# ProPrj_JLINK-OB__2025-09-20.net
KiCad netlist of a schematic drawn in EasyEDA Pro
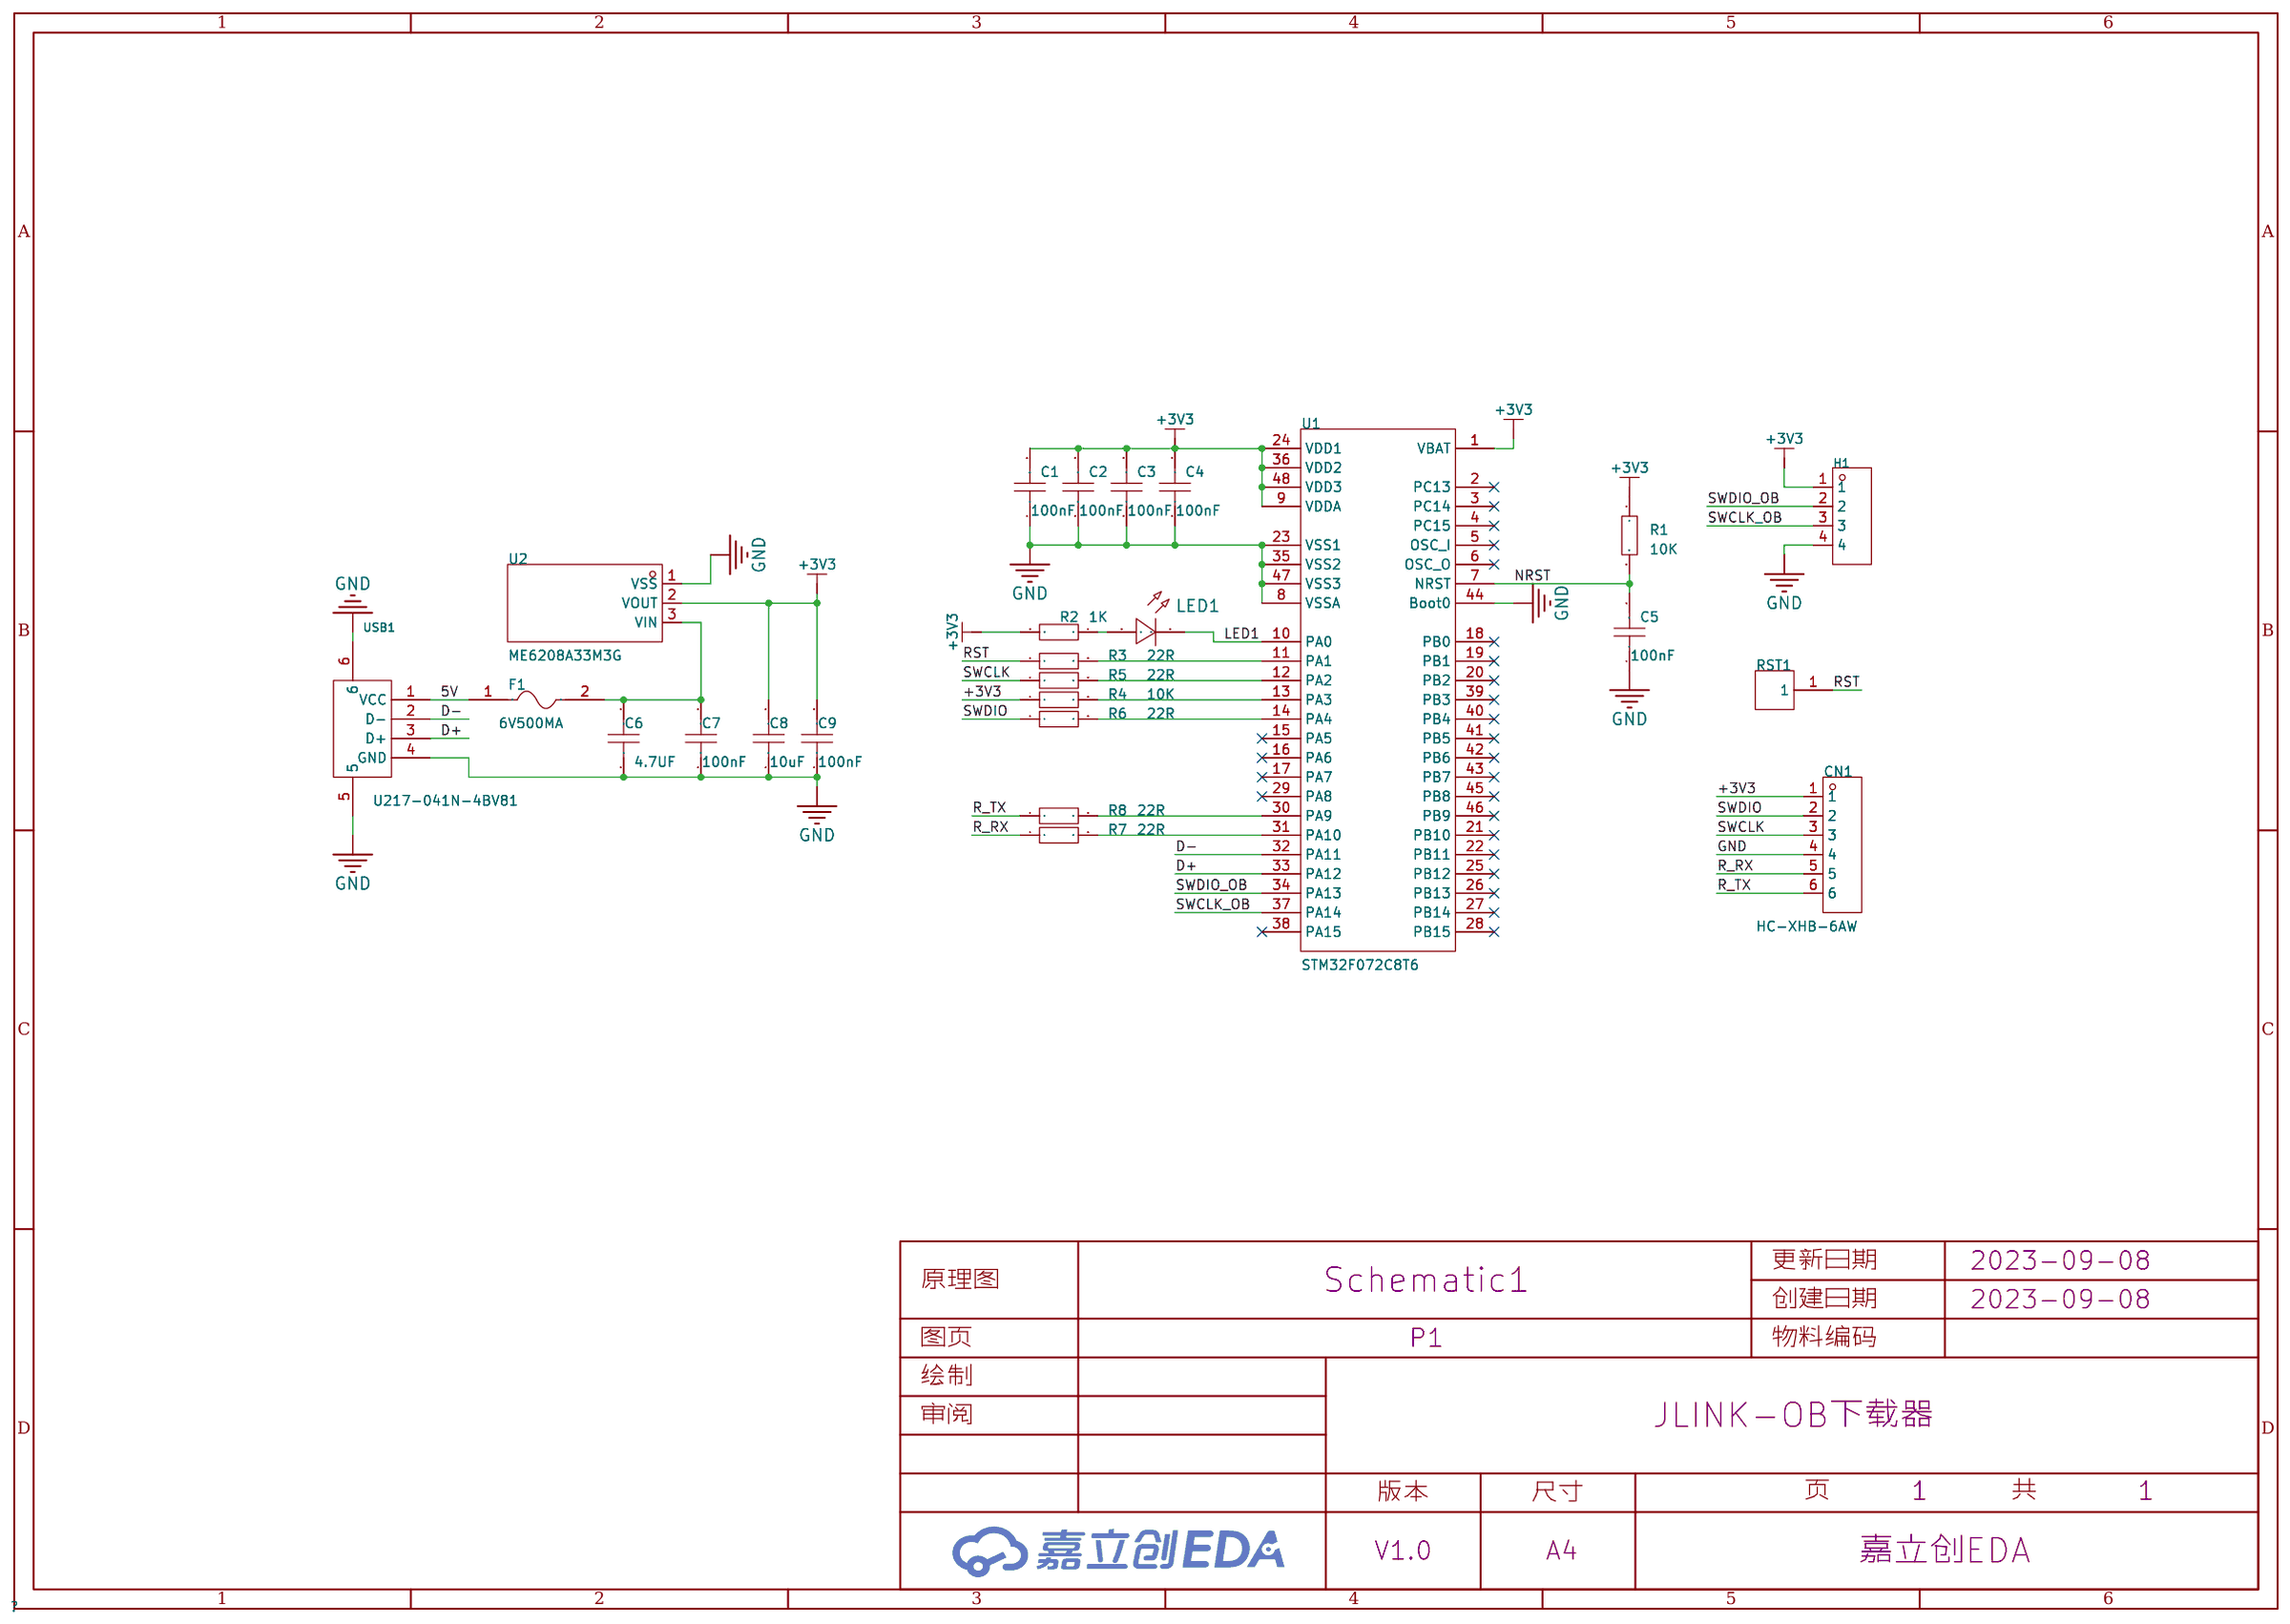
[diagram p0: schematic sheet]

(export (version "E")
  (design (tool "Eeschema 10.0.6"))
  (components
    (comp (ref "C1")
      (value "100nF")
      (footprint "easyedapro:C0603")
      (libsource (lib "easyedapro") (part "CapAcitance"))
    )
    (comp (ref "C2")
      (value "100nF")
      (footprint "easyedapro:C0603")
      (libsource (lib "easyedapro") (part "CapAcitance"))
    )
    (comp (ref "C3")
      (value "100nF")
      (footprint "easyedapro:C0603")
      (libsource (lib "easyedapro") (part "CapAcitance"))
    )
    (comp (ref "C4")
      (value "100nF")
      (footprint "easyedapro:C0603")
      (libsource (lib "easyedapro") (part "CapAcitance"))
    )
    (comp (ref "C5")
      (value "100nF")
      (footprint "easyedapro:C0603")
      (libsource (lib "easyedapro") (part "CapAcitance"))
    )
    (comp (ref "C6")
      (value "4.7UF")
      (footprint "easyedapro:C0603")
      (libsource (lib "easyedapro") (part "CapAcitance"))
    )
    (comp (ref "C7")
      (value "100nF")
      (footprint "easyedapro:C0603")
      (libsource (lib "easyedapro") (part "CapAcitance"))
    )
    (comp (ref "C8")
      (value "10uF")
      (footprint "easyedapro:C0603")
      (libsource (lib "easyedapro") (part "CapAcitance"))
    )
    (comp (ref "C9")
      (value "100nF")
      (footprint "easyedapro:C0603")
      (libsource (lib "easyedapro") (part "CapAcitance"))
    )
    (comp (ref "CN1")
      (value "HC-XHB-6AW")
      (footprint "easyedapro:CONN-TH_6P-P2.50_HCTL_HC-XHB-6AW")
      (description "参考系列:-;间距:2.5mm;插针结构:1x6P;排数:1;每排PIN数:6;行距:-;公母:公型插针;安装方式:弯插;额定电流:3A;工作温度范围:-25°C~+85°C;")
      (fields (field (name "Manufacturer") "HCTL(华灿天禄)"))
      (libsource (lib "easyedapro") (part "HC-XHB-6AW"))
    )
    (comp (ref "F1")
      (value "6V500MA")
      (footprint "easyedapro:F0805")
      (description "最大电压:24V;最大电流:100A;保持电流:100mA;跳闸电流:300mA;")
      (fields (field (name "Manufacturer") "台湾陆海"))
      (libsource (lib "easyedapro") (part "SMD0805-010-24V"))
    )
    (comp (ref "H1")
      (value "~")
      (footprint "easyedapro:HDR-TH_4P-P2.54-V-F")
      (libsource (lib "easyedapro") (part "2.54-1*4P母"))
    )
    (comp (ref "LED1")
      (value "~")
      (footprint "easyedapro:LED_0603")
      (libsource (lib "easyedapro") (part "LED_R"))
    )
    (comp (ref "R1") (value "10K") (footprint "easyedapro:R0603") (libsource (lib "easyedapro") (part "电阻")))
    (comp (ref "R2") (value "1K") (footprint "easyedapro:R0603") (libsource (lib "easyedapro") (part "电阻")))
    (comp (ref "R3") (value "22R") (footprint "easyedapro:R0603") (libsource (lib "easyedapro") (part "电阻")))
    (comp (ref "R4") (value "10K") (footprint "easyedapro:R0603") (libsource (lib "easyedapro") (part "电阻")))
    (comp (ref "R5") (value "22R") (footprint "easyedapro:R0603") (libsource (lib "easyedapro") (part "电阻")))
    (comp (ref "R6") (value "22R") (footprint "easyedapro:R0603") (libsource (lib "easyedapro") (part "电阻")))
    (comp (ref "R7") (value "22R") (footprint "easyedapro:R0603") (libsource (lib "easyedapro") (part "电阻")))
    (comp (ref "R8") (value "22R") (footprint "easyedapro:R0603") (libsource (lib "easyedapro") (part "电阻")))
    (comp (ref "RST1")
      (value "~")
      (footprint "easyedapro:PAD_1.5*1.5MM")
      (libsource (lib "easyedapro") (part "测试点1.5x1.5mm"))
    )
    (comp (ref "U1")
      (value "STM32F072C8T6")
      (footprint "easyedapro:LQFP-48_L7.0-W7.0-P0.50-LS9.0-BL")
      (fields (field (name "Manufacturer") "ST(意法半导体)"))
      (libsource (lib "easyedapro") (part "STM32F072C8T6"))
    )
    (comp (ref "U2")
      (value "ME6208A33M3G")
      (footprint "easyedapro:SOT-23-3_L2.9-W1.3-P1.90-LS2.4-BR")
      (description "输出类型:固定;输出极性:正;最大输入电压:18V;输出电压:3.3V;输出电流:200mA;电源纹波抑制比(PSRR):-;")
      (fields (field (name "Manufacturer") "MICRONE(南京微盟)"))
      (libsource (lib "easyedapro") (part "ME6208A33M3G"))
    )
    (comp (ref "USB1")
      (value "U217-041N-4BV81")
      (footprint "easyedapro:USB-A-SMD_U217-041N-4BV81")
      (fields (field (name "Manufacturer") "XKB Connectivity(中国星坤)"))
      (libsource (lib "easyedapro") (part "U217-04XN-XXR84"))
    )
  )
  (nets
    (net (code "1") (name "+3V3") (class "Default")
      (node (ref "C1") (pin "2") (pinfunction "2_2") (pintype "input"))
      (node (ref "C2") (pin "2") (pinfunction "2_2") (pintype "input"))
      (node (ref "C3") (pin "2") (pinfunction "2_2") (pintype "input"))
      (node (ref "C4") (pin "2") (pinfunction "2_2") (pintype "input"))
      (node (ref "C8") (pin "2") (pinfunction "2_2") (pintype "input"))
      (node (ref "C9") (pin "2") (pinfunction "2_2") (pintype "input"))
      (node (ref "CN1") (pin "1") (pinfunction "1_1") (pintype "input"))
      (node (ref "H1") (pin "1") (pinfunction "1_1") (pintype "input"))
      (node (ref "R1") (pin "1") (pinfunction "1_1") (pintype "input"))
      (node (ref "R2") (pin "2") (pinfunction "2_2") (pintype "input"))
      (node (ref "R4") (pin "1") (pinfunction "1_1") (pintype "input"))
      (node (ref "U1") (pin "1") (pinfunction "VBAT_1") (pintype "input"))
      (node (ref "U1") (pin "24") (pinfunction "VDD1_24") (pintype "input"))
      (node (ref "U1") (pin "36") (pinfunction "VDD2_36") (pintype "input"))
      (node (ref "U1") (pin "48") (pinfunction "VDD3_48") (pintype "input"))
      (node (ref "U1") (pin "9") (pinfunction "VDDA_9") (pintype "input"))
      (node (ref "U2") (pin "2") (pinfunction "VOUT_2") (pintype "input"))
    )
    (net (code "2") (name "/5V") (class "Default")
      (node (ref "F1") (pin "1") (pinfunction "1_1") (pintype "input"))
      (node (ref "USB1") (pin "1") (pinfunction "VCC_1") (pintype "input"))
    )
    (net (code "3") (name "/D+") (class "Default")
      (node (ref "U1") (pin "33") (pinfunction "PA12_33") (pintype "input"))
      (node (ref "USB1") (pin "3") (pinfunction "D+_3") (pintype "input"))
    )
    (net (code "4") (name "/D-") (class "Default")
      (node (ref "U1") (pin "32") (pinfunction "PA11_32") (pintype "input"))
      (node (ref "USB1") (pin "2") (pinfunction "D-_2") (pintype "input"))
    )
    (net (code "5") (name "/LED1") (class "Default")
      (node (ref "LED1") (pin "1") (pinfunction "C_1") (pintype "input"))
      (node (ref "U1") (pin "10") (pinfunction "PA0_10") (pintype "input"))
    )
    (net (code "6") (name "/NRST") (class "Default")
      (node (ref "C5") (pin "2") (pinfunction "2_2") (pintype "input"))
      (node (ref "R1") (pin "2") (pinfunction "2_2") (pintype "input"))
      (node (ref "U1") (pin "7") (pinfunction "NRST_7") (pintype "input"))
    )
    (net (code "7") (name "/RST") (class "Default")
      (node (ref "R3") (pin "1") (pinfunction "1_1") (pintype "input"))
      (node (ref "RST1") (pin "1") (pinfunction "1_1") (pintype "input"))
    )
    (net (code "8") (name "/R_RX") (class "Default")
      (node (ref "CN1") (pin "5") (pinfunction "5_5") (pintype "input"))
      (node (ref "R7") (pin "1") (pinfunction "1_1") (pintype "input"))
    )
    (net (code "9") (name "/R_TX") (class "Default")
      (node (ref "CN1") (pin "6") (pinfunction "6_6") (pintype "input"))
      (node (ref "R8") (pin "1") (pinfunction "1_1") (pintype "input"))
    )
    (net (code "10") (name "/SWCLK") (class "Default")
      (node (ref "CN1") (pin "3") (pinfunction "3_3") (pintype "input"))
      (node (ref "R5") (pin "1") (pinfunction "1_1") (pintype "input"))
    )
    (net (code "11") (name "/SWCLK_OB") (class "Default")
      (node (ref "H1") (pin "3") (pinfunction "3_3") (pintype "input"))
      (node (ref "U1") (pin "37") (pinfunction "PA14_37") (pintype "input"))
    )
    (net (code "12") (name "/SWDIO") (class "Default")
      (node (ref "CN1") (pin "2") (pinfunction "2_2") (pintype "input"))
      (node (ref "R6") (pin "1") (pinfunction "1_1") (pintype "input"))
    )
    (net (code "13") (name "/SWDIO_OB") (class "Default")
      (node (ref "H1") (pin "2") (pinfunction "2_2") (pintype "input"))
      (node (ref "U1") (pin "34") (pinfunction "PA13_34") (pintype "input"))
    )
    (net (code "14") (name "GND") (class "Default")
      (node (ref "C1") (pin "1") (pinfunction "1_1") (pintype "input"))
      (node (ref "C2") (pin "1") (pinfunction "1_1") (pintype "input"))
      (node (ref "C3") (pin "1") (pinfunction "1_1") (pintype "input"))
      (node (ref "C4") (pin "1") (pinfunction "1_1") (pintype "input"))
      (node (ref "C5") (pin "1") (pinfunction "1_1") (pintype "input"))
      (node (ref "C6") (pin "1") (pinfunction "1_1") (pintype "input"))
      (node (ref "C7") (pin "1") (pinfunction "1_1") (pintype "input"))
      (node (ref "C8") (pin "1") (pinfunction "1_1") (pintype "input"))
      (node (ref "C9") (pin "1") (pinfunction "1_1") (pintype "input"))
      (node (ref "CN1") (pin "4") (pinfunction "4_4") (pintype "input"))
      (node (ref "H1") (pin "4") (pinfunction "4_4") (pintype "input"))
      (node (ref "U1") (pin "23") (pinfunction "VSS1_23") (pintype "input"))
      (node (ref "U1") (pin "35") (pinfunction "VSS2_35") (pintype "input"))
      (node (ref "U1") (pin "44") (pinfunction "Boot0_44") (pintype "input"))
      (node (ref "U1") (pin "47") (pinfunction "VSS3_47") (pintype "input"))
      (node (ref "U1") (pin "8") (pinfunction "VSSA_8") (pintype "input"))
      (node (ref "U2") (pin "1") (pinfunction "VSS_1") (pintype "input"))
      (node (ref "USB1") (pin "4") (pinfunction "GND_4") (pintype "input"))
      (node (ref "USB1") (pin "5") (pinfunction "5_5") (pintype "input"))
      (node (ref "USB1") (pin "6") (pinfunction "6_6") (pintype "input"))
    )
    (net (code "15") (name "Net-(LED1-A)") (class "Default")
      (node (ref "LED1") (pin "2") (pinfunction "A_2") (pintype "input"))
      (node (ref "R2") (pin "1") (pinfunction "1_1") (pintype "input"))
    )
    (net (code "16") (name "Net-(U1-PA1)") (class "Default")
      (node (ref "R3") (pin "2") (pinfunction "2_2") (pintype "input"))
      (node (ref "U1") (pin "11") (pinfunction "PA1_11") (pintype "input"))
    )
    (net (code "17") (name "Net-(U1-PA2)") (class "Default")
      (node (ref "R5") (pin "2") (pinfunction "2_2") (pintype "input"))
      (node (ref "U1") (pin "12") (pinfunction "PA2_12") (pintype "input"))
    )
    (net (code "18") (name "Net-(U1-PA3)") (class "Default")
      (node (ref "R4") (pin "2") (pinfunction "2_2") (pintype "input"))
      (node (ref "U1") (pin "13") (pinfunction "PA3_13") (pintype "input"))
    )
    (net (code "19") (name "Net-(U1-PA4)") (class "Default")
      (node (ref "R6") (pin "2") (pinfunction "2_2") (pintype "input"))
      (node (ref "U1") (pin "14") (pinfunction "PA4_14") (pintype "input"))
    )
    (net (code "20") (name "Net-(U1-PA9)") (class "Default")
      (node (ref "R8") (pin "2") (pinfunction "2_2") (pintype "input"))
      (node (ref "U1") (pin "30") (pinfunction "PA9_30") (pintype "input"))
    )
    (net (code "21") (name "Net-(U1-PA10)") (class "Default")
      (node (ref "R7") (pin "2") (pinfunction "2_2") (pintype "input"))
      (node (ref "U1") (pin "31") (pinfunction "PA10_31") (pintype "input"))
    )
    (net (code "22") (name "Net-(U2-VIN)") (class "Default")
      (node (ref "C6") (pin "2") (pinfunction "2_2") (pintype "input"))
      (node (ref "C7") (pin "2") (pinfunction "2_2") (pintype "input"))
      (node (ref "F1") (pin "2") (pinfunction "2_2") (pintype "input"))
      (node (ref "U2") (pin "3") (pinfunction "VIN_3") (pintype "input"))
    )
    (net (code "23") (name "unconnected-(U1-OSC_I-Pad5)") (class "Default")
      (node (ref "U1") (pin "5") (pinfunction "OSC_I_5") (pintype "input+no_connect"))
    )
    (net (code "24") (name "unconnected-(U1-OSC_O-Pad6)") (class "Default")
      (node (ref "U1") (pin "6") (pinfunction "OSC_O_6") (pintype "input+no_connect"))
    )
    (net (code "25") (name "unconnected-(U1-PA5-Pad15)") (class "Default")
      (node (ref "U1") (pin "15") (pinfunction "PA5_15") (pintype "input+no_connect"))
    )
    (net (code "26") (name "unconnected-(U1-PA6-Pad16)") (class "Default")
      (node (ref "U1") (pin "16") (pinfunction "PA6_16") (pintype "input+no_connect"))
    )
    (net (code "27") (name "unconnected-(U1-PA7-Pad17)") (class "Default")
      (node (ref "U1") (pin "17") (pinfunction "PA7_17") (pintype "input+no_connect"))
    )
    (net (code "28") (name "unconnected-(U1-PA8-Pad29)") (class "Default")
      (node (ref "U1") (pin "29") (pinfunction "PA8_29") (pintype "input+no_connect"))
    )
    (net (code "29") (name "unconnected-(U1-PA15-Pad38)") (class "Default")
      (node (ref "U1") (pin "38") (pinfunction "PA15_38") (pintype "input+no_connect"))
    )
    (net (code "30") (name "unconnected-(U1-PB0-Pad18)") (class "Default")
      (node (ref "U1") (pin "18") (pinfunction "PB0_18") (pintype "input+no_connect"))
    )
    (net (code "31") (name "unconnected-(U1-PB1-Pad19)") (class "Default")
      (node (ref "U1") (pin "19") (pinfunction "PB1_19") (pintype "input+no_connect"))
    )
    (net (code "32") (name "unconnected-(U1-PB2-Pad20)") (class "Default")
      (node (ref "U1") (pin "20") (pinfunction "PB2_20") (pintype "input+no_connect"))
    )
    (net (code "33") (name "unconnected-(U1-PB3-Pad39)") (class "Default")
      (node (ref "U1") (pin "39") (pinfunction "PB3_39") (pintype "input+no_connect"))
    )
    (net (code "34") (name "unconnected-(U1-PB4-Pad40)") (class "Default")
      (node (ref "U1") (pin "40") (pinfunction "PB4_40") (pintype "input+no_connect"))
    )
    (net (code "35") (name "unconnected-(U1-PB5-Pad41)") (class "Default")
      (node (ref "U1") (pin "41") (pinfunction "PB5_41") (pintype "input+no_connect"))
    )
    (net (code "36") (name "unconnected-(U1-PB6-Pad42)") (class "Default")
      (node (ref "U1") (pin "42") (pinfunction "PB6_42") (pintype "input+no_connect"))
    )
    (net (code "37") (name "unconnected-(U1-PB7-Pad43)") (class "Default")
      (node (ref "U1") (pin "43") (pinfunction "PB7_43") (pintype "input+no_connect"))
    )
    (net (code "38") (name "unconnected-(U1-PB8-Pad45)") (class "Default")
      (node (ref "U1") (pin "45") (pinfunction "PB8_45") (pintype "input+no_connect"))
    )
    (net (code "39") (name "unconnected-(U1-PB9-Pad46)") (class "Default")
      (node (ref "U1") (pin "46") (pinfunction "PB9_46") (pintype "input+no_connect"))
    )
    (net (code "40") (name "unconnected-(U1-PB10-Pad21)") (class "Default")
      (node (ref "U1") (pin "21") (pinfunction "PB10_21") (pintype "input+no_connect"))
    )
    (net (code "41") (name "unconnected-(U1-PB11-Pad22)") (class "Default")
      (node (ref "U1") (pin "22") (pinfunction "PB11_22") (pintype "input+no_connect"))
    )
    (net (code "42") (name "unconnected-(U1-PB12-Pad25)") (class "Default")
      (node (ref "U1") (pin "25") (pinfunction "PB12_25") (pintype "input+no_connect"))
    )
    (net (code "43") (name "unconnected-(U1-PB13-Pad26)") (class "Default")
      (node (ref "U1") (pin "26") (pinfunction "PB13_26") (pintype "input+no_connect"))
    )
    (net (code "44") (name "unconnected-(U1-PB14-Pad27)") (class "Default")
      (node (ref "U1") (pin "27") (pinfunction "PB14_27") (pintype "input+no_connect"))
    )
    (net (code "45") (name "unconnected-(U1-PB15-Pad28)") (class "Default")
      (node (ref "U1") (pin "28") (pinfunction "PB15_28") (pintype "input+no_connect"))
    )
    (net (code "46") (name "unconnected-(U1-PC13-Pad2)") (class "Default")
      (node (ref "U1") (pin "2") (pinfunction "PC13_2") (pintype "input+no_connect"))
    )
    (net (code "47") (name "unconnected-(U1-PC14-Pad3)") (class "Default")
      (node (ref "U1") (pin "3") (pinfunction "PC14_3") (pintype "input+no_connect"))
    )
    (net (code "48") (name "unconnected-(U1-PC15-Pad4)") (class "Default")
      (node (ref "U1") (pin "4") (pinfunction "PC15_4") (pintype "input+no_connect"))
    )
  )
)
